# Mega_Stepper_Shield_Integrated.net
KiCad netlist of a schematic drawn in EAGLE
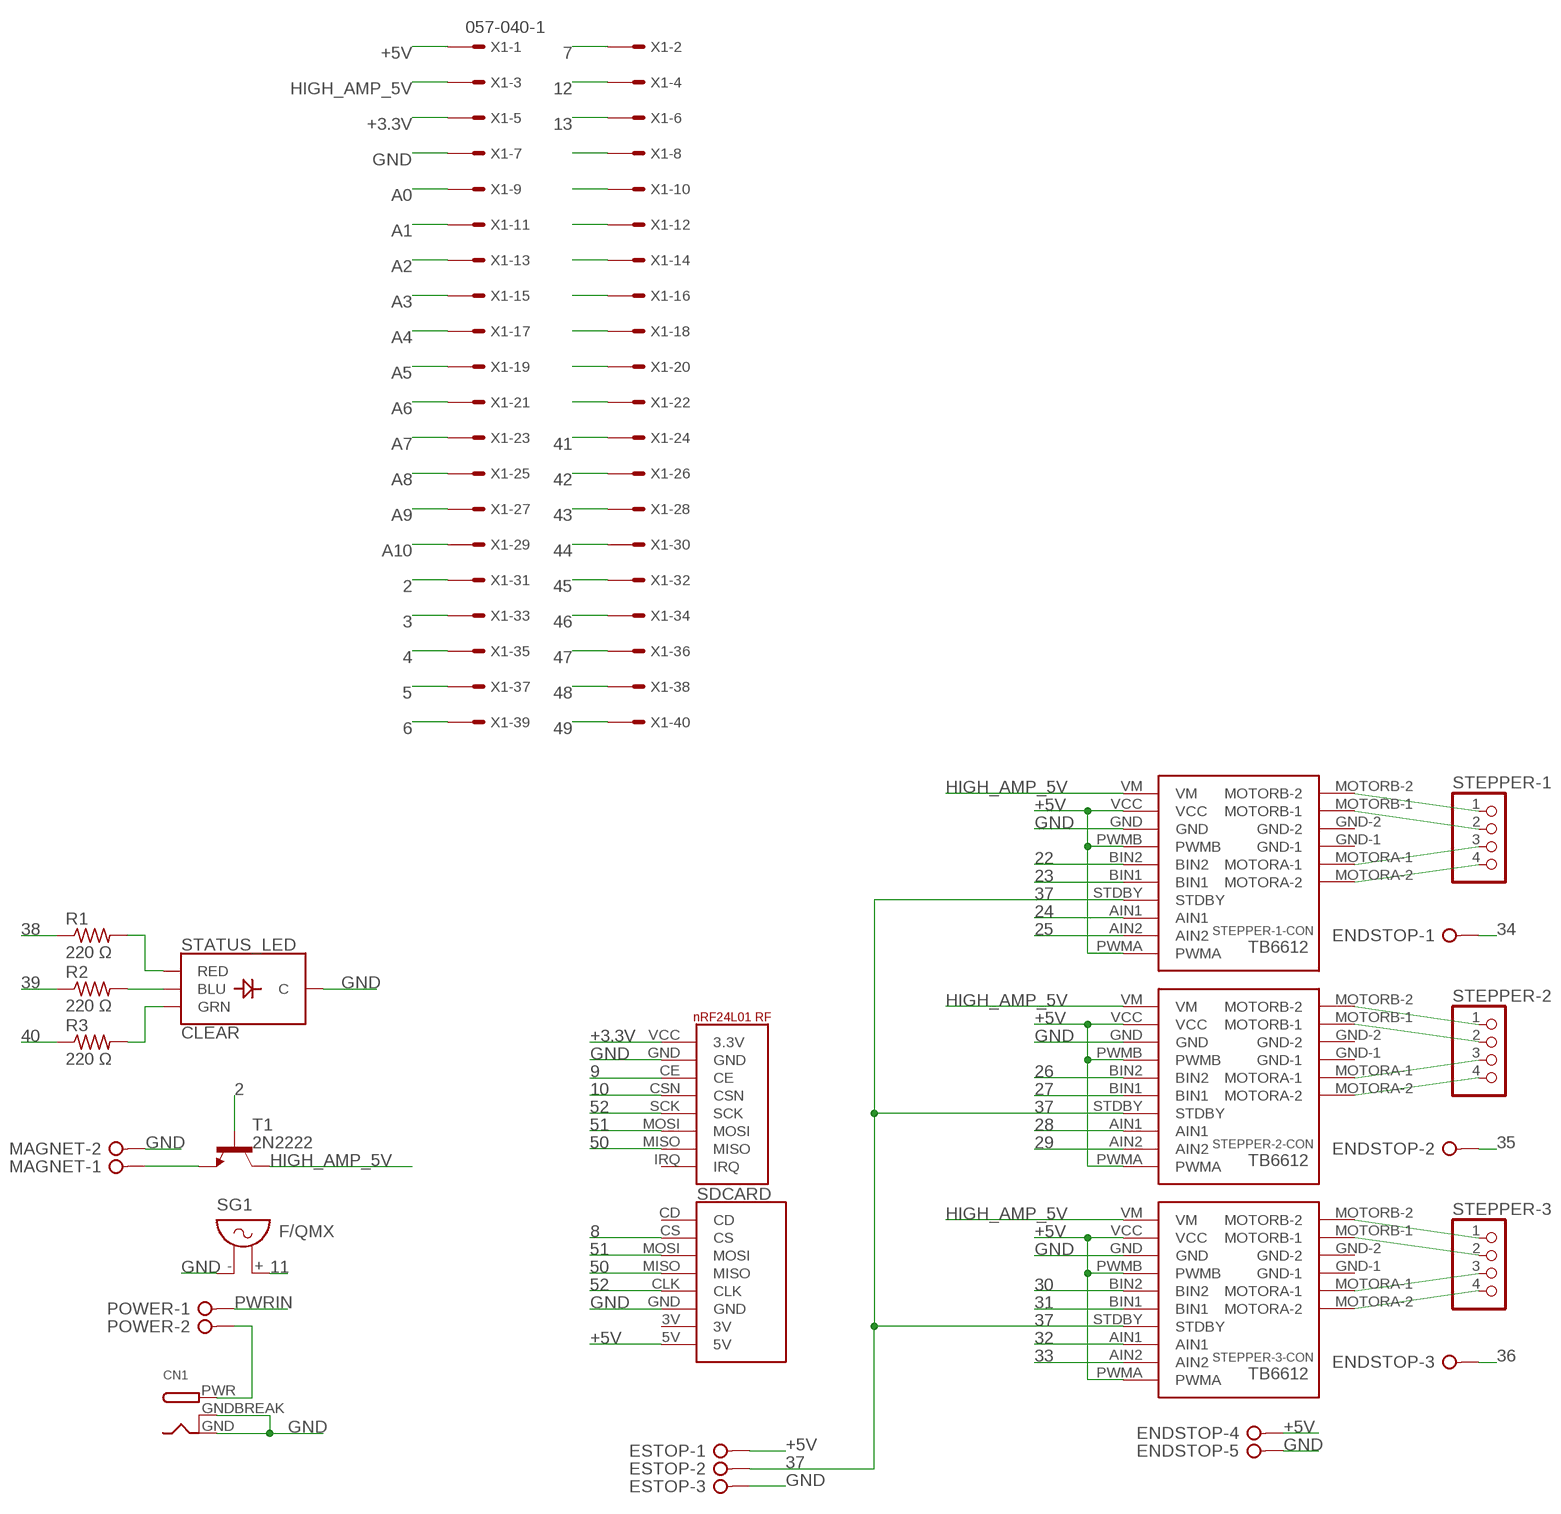
[diagram p0: schematic, sheet 1]
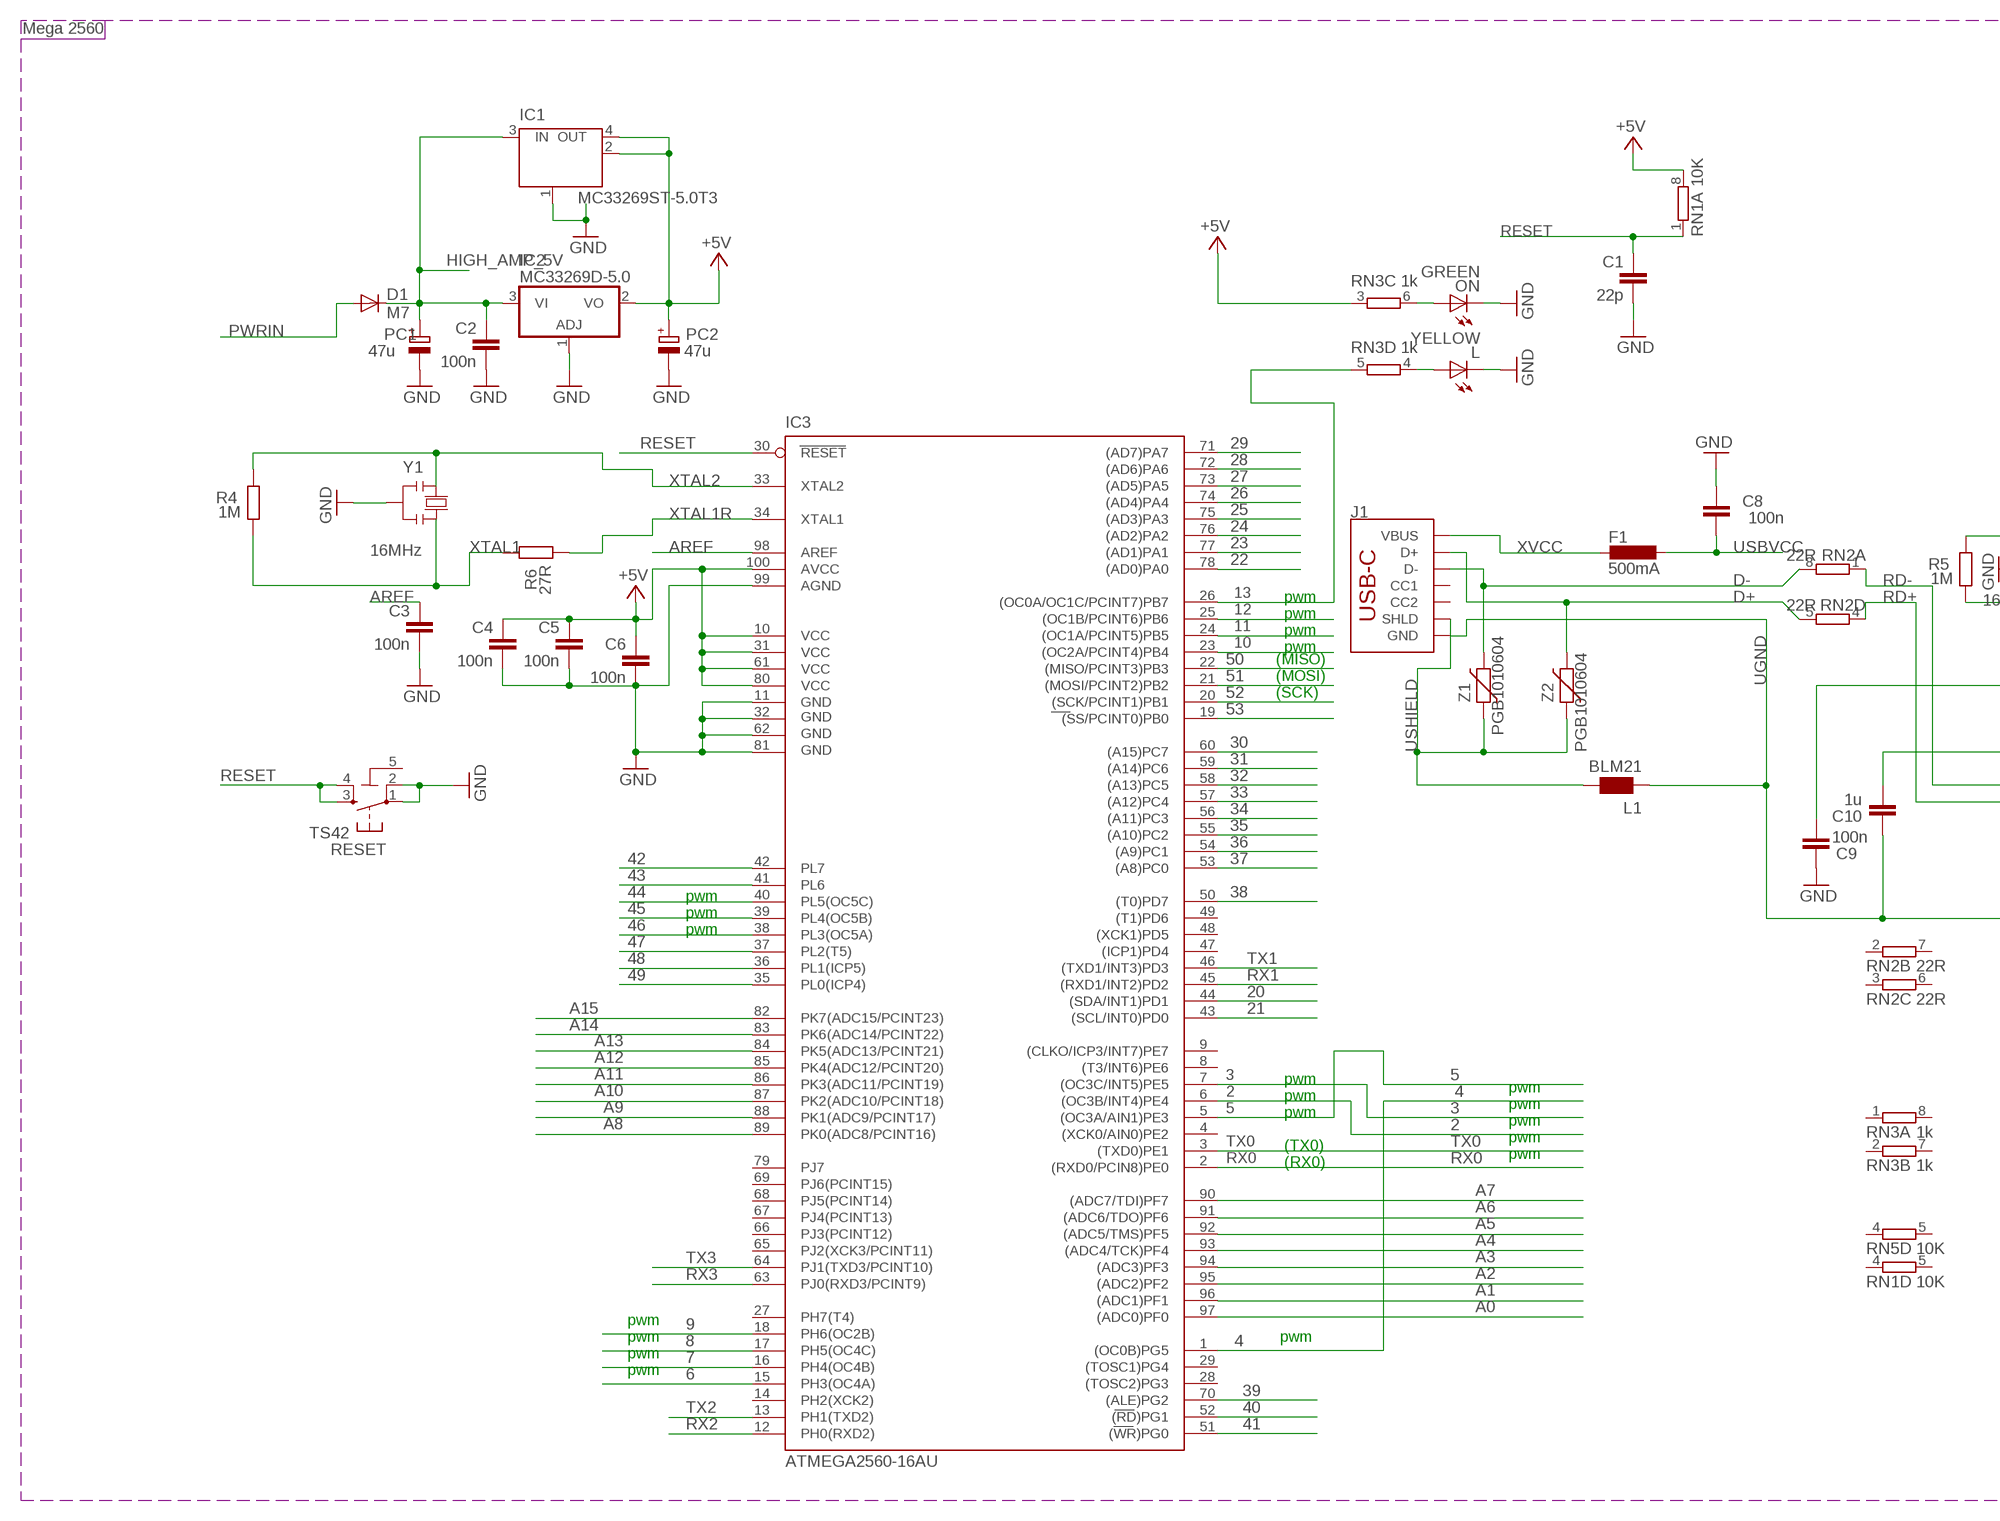
[diagram p1: schematic, sheet 2, part 1 of 2]
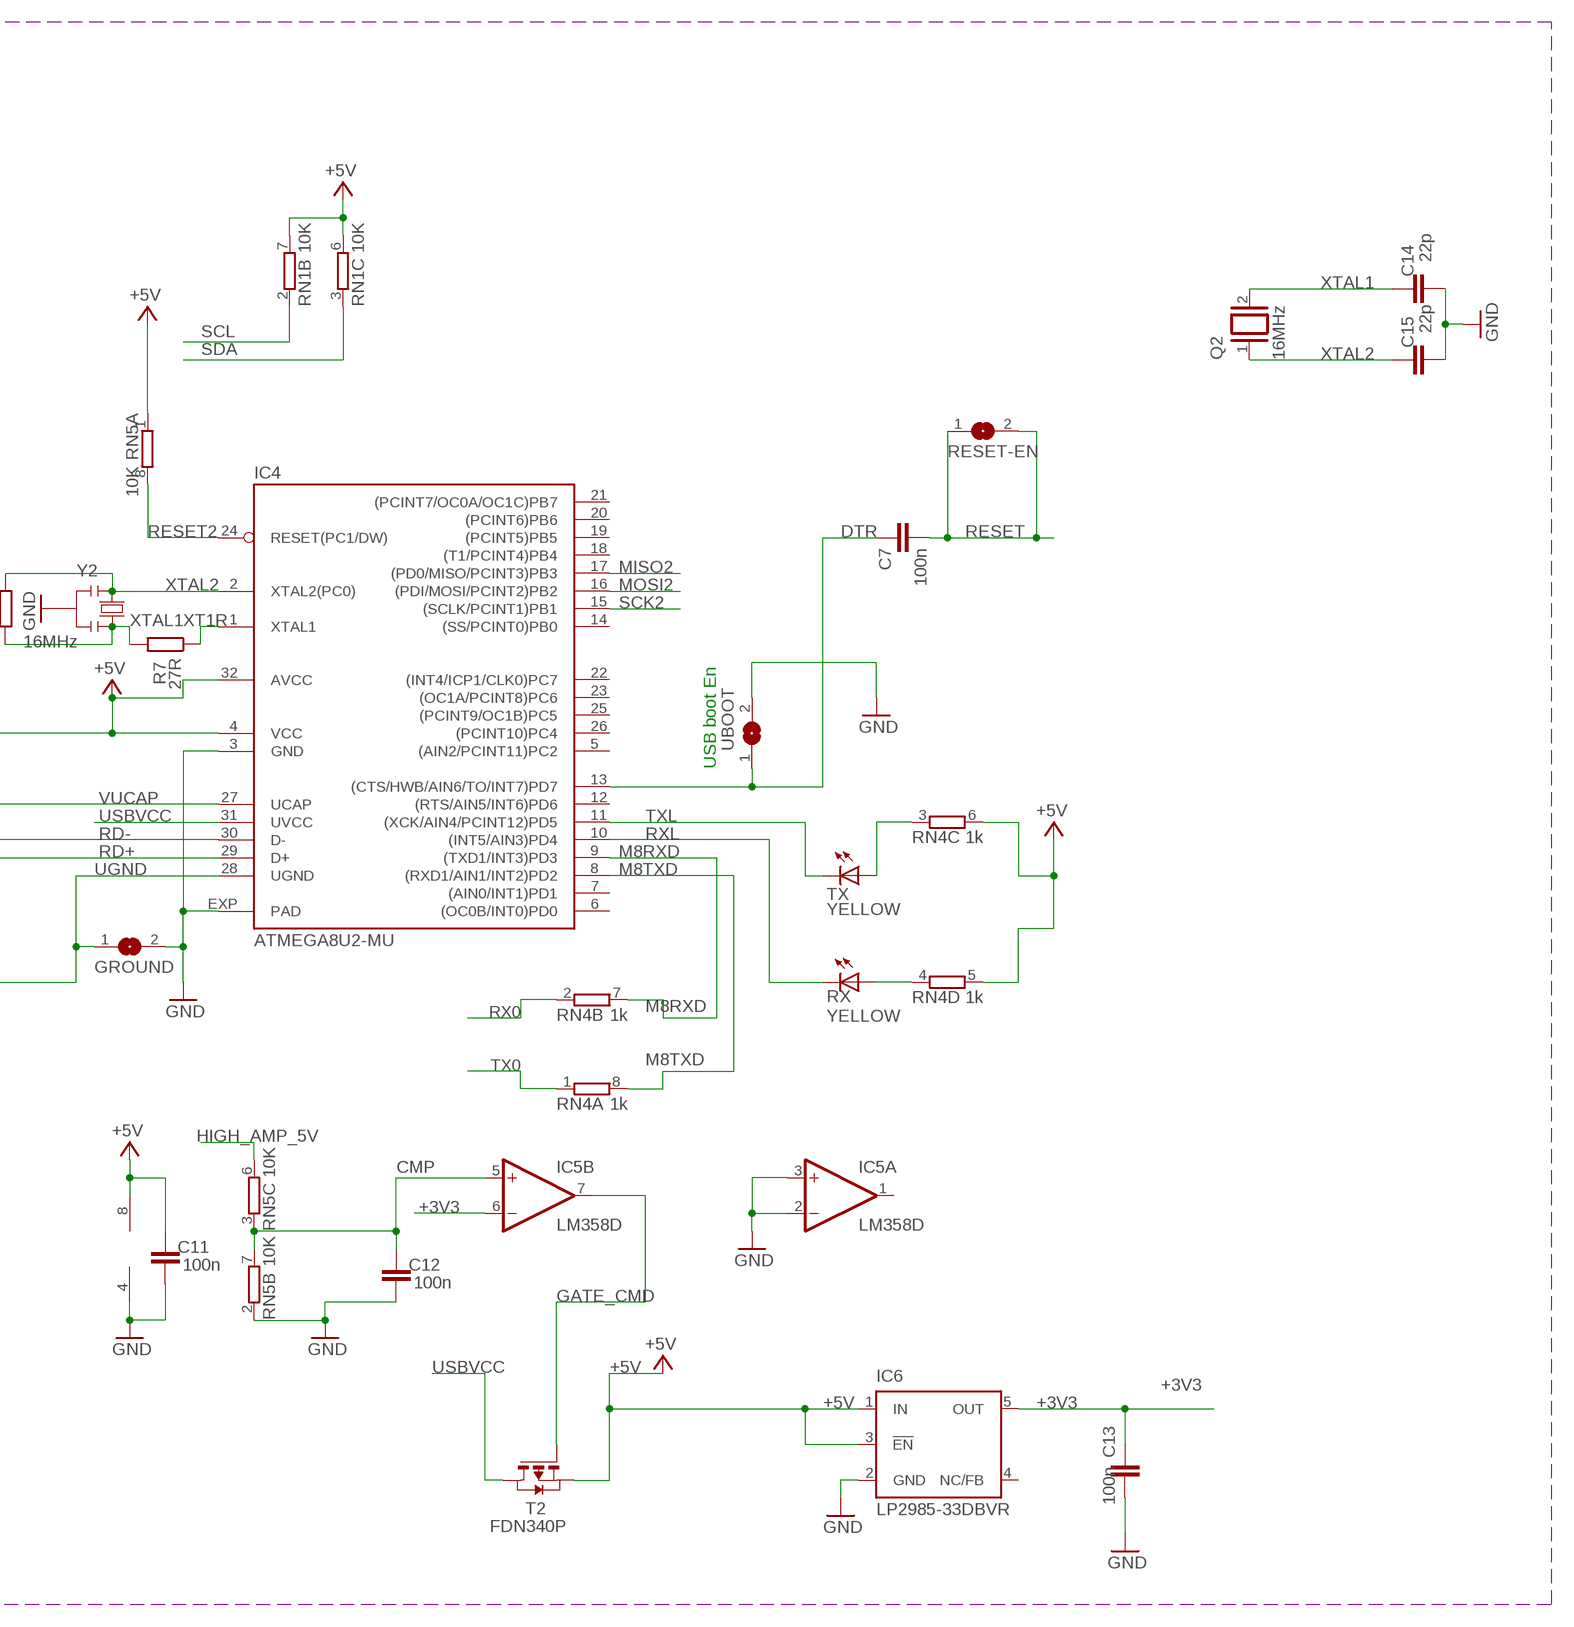
[diagram p2: schematic, sheet 2, part 2 of 2]

(export (version "E")
  (design (tool "Eeschema 10.0.6"))
  (components
    (comp (ref "CN1")
      (value "DCBARRELPTH")
      (footprint "eagle-import:DCJACK_2MM_PTH")
      (libsource (lib "eagle-import") (part "DCBARRELPTH"))
    )
    (comp (ref "ENDSTOP")
      (value "W237-05P")
      (footprint "eagle-import:W237-5P")
      (libsource (lib "eagle-import") (part "W237-05P"))
    )
    (comp (ref "ESTOP")
      (value "W237-3E")
      (footprint "eagle-import:W237-3E")
      (libsource (lib "eagle-import") (part "W237-3E"))
    )
    (comp (ref "MAGNET")
      (value "W237-02P")
      (footprint "eagle-import:W237-132")
      (libsource (lib "eagle-import") (part "W237-02P"))
    )
    (comp (ref "POWER")
      (value "W237-02P")
      (footprint "eagle-import:W237-132")
      (libsource (lib "eagle-import") (part "W237-02P"))
    )
    (comp (ref "R1")
      (value "220 Ω")
      (footprint "eagle-import:0204_7")
      (libsource (lib "eagle-import") (part "R-US_0204/7"))
    )
    (comp (ref "R2")
      (value "220 Ω")
      (footprint "eagle-import:0204_7")
      (libsource (lib "eagle-import") (part "R-US_0204/7"))
    )
    (comp (ref "R3")
      (value "220 Ω")
      (footprint "eagle-import:0204_7")
      (libsource (lib "eagle-import") (part "R-US_0204/7"))
    )
    (comp (ref "SDCARD")
      (value "MICRO_SD_BREAKOUT")
      (footprint "eagle-import:MICROSDCARDBREAKOUT")
      (libsource (lib "eagle-import") (part "MICRO_SD_BREAKOUT"))
    )
    (comp (ref "SG1")
      (value "F/QMX")
      (footprint "eagle-import:F_QMX")
      (libsource (lib "eagle-import") (part "F/QMX"))
    )
    (comp (ref "STATUS_LED")
      (value "CLEAR")
      (footprint "eagle-import:LED-RGB-THRU")
      (libsource (lib "eagle-import") (part "LED-RGB-CCCLEAR"))
    )
    (comp (ref "STEPPER-1")
      (value "PINHD-1X4")
      (footprint "eagle-import:1X04")
      (libsource (lib "eagle-import") (part "PINHD-1X4"))
    )
    (comp (ref "STEPPER-1-CON")
      (value "TB6612-BREAKOUT-MOTOR-CONTROLLER")
      (footprint "eagle-import:TB6612-HEADERS")
      (libsource (lib "eagle-import") (part "TB6612-BREAKOUT-MOTOR-CONTROLLER"))
    )
    (comp (ref "STEPPER-2")
      (value "PINHD-1X4")
      (footprint "eagle-import:1X04")
      (libsource (lib "eagle-import") (part "PINHD-1X4"))
    )
    (comp (ref "STEPPER-2-CON")
      (value "TB6612-BREAKOUT-MOTOR-CONTROLLER")
      (footprint "eagle-import:TB6612-HEADERS")
      (libsource (lib "eagle-import") (part "TB6612-BREAKOUT-MOTOR-CONTROLLER"))
    )
    (comp (ref "STEPPER-3")
      (value "PINHD-1X4")
      (footprint "eagle-import:1X04")
      (libsource (lib "eagle-import") (part "PINHD-1X4"))
    )
    (comp (ref "STEPPER-3-CON")
      (value "TB6612-BREAKOUT-MOTOR-CONTROLLER")
      (footprint "eagle-import:TB6612-HEADERS")
      (libsource (lib "eagle-import") (part "TB6612-BREAKOUT-MOTOR-CONTROLLER"))
    )
    (comp (ref "T1")
      (value "2N2222")
      (footprint "eagle-import:TO92-EBC-OVAL")
      (libsource (lib "eagle-import") (part "2N2222"))
    )
    (comp (ref "U$1")
      (value "NRF24L01_RF_MODULE")
      (footprint "eagle-import:NRF24L01RF")
      (libsource (lib "eagle-import") (part "NRF24L01_RF_MODULE"))
    )
    (comp (ref "X1")
      (value "057-040-1")
      (footprint "eagle-import:057-040-1")
      (libsource (lib "eagle-import") (part "057-040-1"))
    )
    (comp (ref "C1")
      (value "22p")
      (footprint "eagle-import:C0603-ROUND")
      (libsource (lib "eagle-import") (part "C-EU0603-RND"))
    )
    (comp (ref "C2")
      (value "100n")
      (footprint "eagle-import:C0603-ROUND")
      (libsource (lib "eagle-import") (part "C-EU0603-RND"))
    )
    (comp (ref "C3")
      (value "100n")
      (footprint "eagle-import:C0603-ROUND")
      (libsource (lib "eagle-import") (part "C-EU0603-RND"))
    )
    (comp (ref "C4")
      (value "100n")
      (footprint "eagle-import:C0603-ROUND")
      (libsource (lib "eagle-import") (part "C-EU0603-RND"))
    )
    (comp (ref "C5")
      (value "100n")
      (footprint "eagle-import:C0603-ROUND")
      (libsource (lib "eagle-import") (part "C-EU0603-RND"))
    )
    (comp (ref "C6")
      (value "100n")
      (footprint "eagle-import:C0603-ROUND")
      (libsource (lib "eagle-import") (part "C-EU0603-RND"))
    )
    (comp (ref "C7")
      (value "100n")
      (footprint "eagle-import:C0603-ROUND")
      (libsource (lib "eagle-import") (part "C-EU0603-RND"))
    )
    (comp (ref "C8")
      (value "100n")
      (footprint "eagle-import:C0603")
      (libsource (lib "eagle-import") (part "rcl_C-EUC0603"))
    )
    (comp (ref "C9")
      (value "100n")
      (footprint "eagle-import:C0603-ROUND")
      (libsource (lib "eagle-import") (part "C-EU0603-RND"))
    )
    (comp (ref "C10")
      (value "1u")
      (footprint "eagle-import:C0603-ROUND")
      (libsource (lib "eagle-import") (part "C-EU0603-RND"))
    )
    (comp (ref "C11")
      (value "100n")
      (footprint "eagle-import:C0603")
      (libsource (lib "eagle-import") (part "rcl_C-EUC0603"))
    )
    (comp (ref "C12")
      (value "100n")
      (footprint "eagle-import:C0603-ROUND")
      (libsource (lib "eagle-import") (part "C-EU0603-RND"))
    )
    (comp (ref "C13")
      (value "100n")
      (footprint "eagle-import:C0603-ROUND")
      (libsource (lib "eagle-import") (part "C-EU0603-RND"))
    )
    (comp (ref "C14")
      (value "22p")
      (footprint "eagle-import:C0603-ROUND")
      (libsource (lib "eagle-import") (part "C-EU0603-RND"))
    )
    (comp (ref "C15")
      (value "22p")
      (footprint "eagle-import:C0603-ROUND")
      (libsource (lib "eagle-import") (part "C-EU0603-RND"))
    )
    (comp (ref "D1")
      (value "M7")
      (footprint "eagle-import:SMB")
      (libsource (lib "eagle-import") (part "DIODE-SMB"))
    )
    (comp (ref "F1")
      (value "500mA")
      (footprint "eagle-import:L1812")
      (libsource (lib "eagle-import") (part "L-EUL1812"))
    )
    (comp (ref "GROUND")
      (value "SJ")
      (footprint "eagle-import:SJ")
      (libsource (lib "eagle-import") (part "SJ"))
    )
    (comp (ref "IC1")
      (value "MC33269ST-5.0T3")
      (footprint "eagle-import:SOT223")
      (libsource (lib "eagle-import") (part "MC33269ST-3.3T3"))
    )
    (comp (ref "IC2")
      (value "MC33269D-5.0")
      (footprint "eagle-import:DPACK")
      (libsource (lib "eagle-import") (part "MC33269?D-5.0"))
    )
    (comp (ref "IC3")
      (value "ATMEGA2560-16AU")
      (footprint "eagle-import:TQFP100")
      (libsource (lib "eagle-import") (part "ATMEGAAU1280-16"))
    )
    (comp (ref "IC4")
      (value "ATMEGA8U2-MU")
      (footprint "eagle-import:QFN32")
      (libsource (lib "eagle-import") (part "ATMEGA8U2-MU"))
    )
    (comp (ref "IC5")
      (value "LM358D")
      (footprint "eagle-import:SO08")
      (libsource (lib "eagle-import") (part "LM358D"))
    )
    (comp (ref "IC6")
      (value "LP2985-33DBVR")
      (footprint "eagle-import:SOT23-DBV")
      (libsource (lib "eagle-import") (part "TPS77033"))
    )
    (comp (ref "J1")
      (value "USB_C_2-LAYER_PADS")
      (footprint "eagle-import:USB-C-16P-2LAYER-PADS")
      (libsource (lib "eagle-import") (part "USB_C_2-LAYER_PADS"))
    )
    (comp (ref "L")
      (value "YELLOW")
      (footprint "eagle-import:CHIP-LED0805")
      (libsource (lib "eagle-import") (part "LEDCHIP-LED0805"))
    )
    (comp (ref "L1")
      (value "BLM21")
      (footprint "eagle-import:0805")
      (libsource (lib "eagle-import") (part "WE-CBF_0805"))
    )
    (comp (ref "ON")
      (value "GREEN")
      (footprint "eagle-import:CHIP-LED0805")
      (libsource (lib "eagle-import") (part "LEDCHIP-LED0805"))
    )
    (comp (ref "PC1")
      (value "47u")
      (footprint "eagle-import:PANASONIC_D")
      (libsource (lib "eagle-import") (part "CPOL-EUD"))
    )
    (comp (ref "PC2")
      (value "47u")
      (footprint "eagle-import:PANASONIC_D")
      (libsource (lib "eagle-import") (part "CPOL-EUD"))
    )
    (comp (ref "Q2")
      (value "16MHz")
      (footprint "eagle-import:QS")
      (libsource (lib "eagle-import") (part "XTAL/S"))
    )
    (comp (ref "R4")
      (value "1M")
      (footprint "eagle-import:R0603-ROUND")
      (libsource (lib "eagle-import") (part "R-EU_R0603"))
    )
    (comp (ref "R5")
      (value "1M")
      (footprint "eagle-import:R0603-ROUND")
      (libsource (lib "eagle-import") (part "R-EU_R0603"))
    )
    (comp (ref "R6")
      (value "27R")
      (footprint "eagle-import:R0603-ROUND")
      (libsource (lib "eagle-import") (part "R-EU_R0603"))
    )
    (comp (ref "R7")
      (value "27R")
      (footprint "eagle-import:R0603-ROUND")
      (libsource (lib "eagle-import") (part "R-EU_R0603"))
    )
    (comp (ref "RESET")
      (value "TS42")
      (footprint "eagle-import:TS42")
      (libsource (lib "eagle-import") (part "TS42"))
    )
    (comp (ref "RESET-EN")
      (value "SJ")
      (footprint "eagle-import:SJ")
      (libsource (lib "eagle-import") (part "SJ"))
    )
    (comp (ref "RN1")
      (value "10K")
      (footprint "eagle-import:CAT16")
      (libsource (lib "eagle-import") (part "4R-NCAT16"))
    )
    (comp (ref "RN2")
      (value "22R")
      (footprint "eagle-import:CAY16")
      (libsource (lib "eagle-import") (part "4R-NCAY16"))
    )
    (comp (ref "RN3")
      (value "1k")
      (footprint "eagle-import:CAY16")
      (libsource (lib "eagle-import") (part "4R-NCAY16"))
    )
    (comp (ref "RN4")
      (value "1k")
      (footprint "eagle-import:CAY16")
      (libsource (lib "eagle-import") (part "4R-NCAY16"))
    )
    (comp (ref "RN5")
      (value "10K")
      (footprint "eagle-import:CAT16")
      (libsource (lib "eagle-import") (part "4R-NCAT16"))
    )
    (comp (ref "RX")
      (value "YELLOW")
      (footprint "eagle-import:CHIP-LED0805")
      (libsource (lib "eagle-import") (part "LEDCHIP-LED0805"))
    )
    (comp (ref "T2")
      (value "FDN340P")
      (footprint "eagle-import:SOT-23")
      (libsource (lib "eagle-import") (part "PMOSSOT23"))
    )
    (comp (ref "TX")
      (value "YELLOW")
      (footprint "eagle-import:CHIP-LED0805")
      (libsource (lib "eagle-import") (part "LEDCHIP-LED0805"))
    )
    (comp (ref "UBOOT")
      (value "SJ")
      (footprint "eagle-import:SJ")
      (libsource (lib "eagle-import") (part "SJ"))
    )
    (comp (ref "Y1")
      (value "16MHz")
      (footprint "eagle-import:RESONATOR")
      (libsource (lib "eagle-import") (part "RESONATORMU"))
    )
    (comp (ref "Y2")
      (value "16MHz")
      (footprint "eagle-import:RESONATOR")
      (libsource (lib "eagle-import") (part "RESONATORMU"))
    )
    (comp (ref "Z1")
      (value "PGB1010604")
      (footprint "eagle-import:CT_CN0603")
      (libsource (lib "eagle-import") (part "VARISTORCN0603"))
    )
    (comp (ref "Z2")
      (value "PGB1010604")
      (footprint "eagle-import:CT_CN0603")
      (libsource (lib "eagle-import") (part "VARISTORCN0603"))
    )
  )
  (nets
    (net (code "1") (name "+3.3V") (class "Default")
      (node (ref "U$1") (pin "VCC") (pinfunction "3.3V_VCC") (pintype "bidirectional"))
      (node (ref "X1") (pin "5") (pinfunction "S_5") (pintype "passive"))
    )
    (net (code "2") (name "+3V3") (class "Default")
      (node (ref "C13") (pin "2") (pinfunction "2_2") (pintype "passive"))
      (node (ref "IC5") (pin "6") (pinfunction "-IN_6") (pintype "input"))
      (node (ref "IC6") (pin "5") (pinfunction "OUT_5") (pintype "passive"))
    )
    (net (code "3") (name "+5V") (class "Default")
      (node (ref "C11") (pin "2") (pinfunction "2_2") (pintype "passive"))
      (node (ref "C4") (pin "1") (pinfunction "1_1") (pintype "passive"))
      (node (ref "C5") (pin "1") (pinfunction "1_1") (pintype "passive"))
      (node (ref "C6") (pin "1") (pinfunction "1_1") (pintype "passive"))
      (node (ref "C9") (pin "1") (pinfunction "1_1") (pintype "passive"))
      (node (ref "ENDSTOP") (pin "4") (pinfunction "KL_4") (pintype "passive"))
      (node (ref "ESTOP") (pin "1") (pinfunction "KL_1") (pintype "passive"))
      (node (ref "IC1") (pin "2") (pinfunction "OUT_2") (pintype "passive"))
      (node (ref "IC1") (pin "4") (pinfunction "OUT_4") (pintype "passive"))
      (node (ref "IC2") (pin "2") (pinfunction "VO_2") (pintype "passive"))
      (node (ref "IC3") (pin "10") (pinfunction "VCC_10") (pintype "power_in"))
      (node (ref "IC3") (pin "100") (pinfunction "AVCC_100") (pintype "power_in"))
      (node (ref "IC3") (pin "31") (pinfunction "VCC1_31") (pintype "power_in"))
      (node (ref "IC3") (pin "61") (pinfunction "VCC2_61") (pintype "power_in"))
      (node (ref "IC3") (pin "80") (pinfunction "VCC3_80") (pintype "power_in"))
      (node (ref "IC4") (pin "32") (pinfunction "AVCC_32") (pintype "power_in"))
      (node (ref "IC4") (pin "4") (pinfunction "VCC_4") (pintype "power_in"))
      (node (ref "IC5") (pin "8") (pinfunction "V+_8") (pintype "power_in"))
      (node (ref "IC6") (pin "1") (pinfunction "IN_1") (pintype "input"))
      (node (ref "IC6") (pin "3") (pinfunction "~{EN}_3") (pintype "input"))
      (node (ref "PC2") (pin "+") (pinfunction "+_+") (pintype "passive"))
      (node (ref "RN1") (pin "6") (pinfunction "2_6") (pintype "passive"))
      (node (ref "RN1") (pin "7") (pinfunction "2_7") (pintype "passive"))
      (node (ref "RN1") (pin "8") (pinfunction "2_8") (pintype "passive"))
      (node (ref "RN3") (pin "3") (pinfunction "1_3") (pintype "passive"))
      (node (ref "RN4") (pin "5") (pinfunction "2_5") (pintype "passive"))
      (node (ref "RN4") (pin "6") (pinfunction "2_6") (pintype "passive"))
      (node (ref "RN5") (pin "1") (pinfunction "1_1") (pintype "passive"))
      (node (ref "SDCARD") (pin "5V") (pinfunction "5V_5V") (pintype "bidirectional"))
      (node (ref "STEPPER-1-CON") (pin "PWMA") (pinfunction "PWMA_PWMA") (pintype "bidirectional"))
      (node (ref "STEPPER-1-CON") (pin "PWMB") (pinfunction "PWMB_PWMB") (pintype "bidirectional"))
      (node (ref "STEPPER-1-CON") (pin "VCC") (pinfunction "VCC_VCC") (pintype "bidirectional"))
      (node (ref "STEPPER-2-CON") (pin "PWMA") (pinfunction "PWMA_PWMA") (pintype "bidirectional"))
      (node (ref "STEPPER-2-CON") (pin "PWMB") (pinfunction "PWMB_PWMB") (pintype "bidirectional"))
      (node (ref "STEPPER-2-CON") (pin "VCC") (pinfunction "VCC_VCC") (pintype "bidirectional"))
      (node (ref "STEPPER-3-CON") (pin "PWMA") (pinfunction "PWMA_PWMA") (pintype "bidirectional"))
      (node (ref "STEPPER-3-CON") (pin "PWMB") (pinfunction "PWMB_PWMB") (pintype "bidirectional"))
      (node (ref "STEPPER-3-CON") (pin "VCC") (pinfunction "VCC_VCC") (pintype "bidirectional"))
      (node (ref "T2") (pin "2") (pinfunction "S_2") (pintype "passive"))
      (node (ref "X1") (pin "1") (pinfunction "S_1") (pintype "passive"))
    )
    (net (code "4") (name "2") (class "Default")
      (node (ref "IC3") (pin "6") (pinfunction "(OC3B/INT4)PE4_6") (pintype "bidirectional"))
      (node (ref "T1") (pin "B") (pinfunction "B_B") (pintype "passive"))
      (node (ref "X1") (pin "31") (pinfunction "S_31") (pintype "passive"))
    )
    (net (code "5") (name "3") (class "Default")
      (node (ref "IC3") (pin "7") (pinfunction "(OC3C/INT5)PE5_7") (pintype "bidirectional"))
      (node (ref "X1") (pin "33") (pinfunction "S_33") (pintype "passive"))
    )
    (net (code "6") (name "4") (class "Default")
      (node (ref "IC3") (pin "1") (pinfunction "(OC0B)PG5_1") (pintype "bidirectional"))
      (node (ref "X1") (pin "35") (pinfunction "S_35") (pintype "passive"))
    )
    (net (code "7") (name "5") (class "Default")
      (node (ref "IC3") (pin "5") (pinfunction "(OC3A/AIN1)PE3_5") (pintype "bidirectional"))
      (node (ref "X1") (pin "37") (pinfunction "S_37") (pintype "passive"))
    )
    (net (code "8") (name "5-GND") (class "Default")
      (node (ref "RESET") (pin "5") (pinfunction "5-GND_5") (pintype "power_in"))
    )
    (net (code "9") (name "6") (class "Default")
      (node (ref "IC3") (pin "15") (pinfunction "PH3(OC4A)_15") (pintype "bidirectional"))
      (node (ref "X1") (pin "39") (pinfunction "S_39") (pintype "passive"))
    )
    (net (code "10") (name "7") (class "Default")
      (node (ref "IC3") (pin "16") (pinfunction "PH4(OC4B)_16") (pintype "bidirectional"))
      (node (ref "X1") (pin "2") (pinfunction "S_2") (pintype "passive"))
    )
    (net (code "11") (name "8") (class "Default")
      (node (ref "IC3") (pin "17") (pinfunction "PH5(OC4C)_17") (pintype "bidirectional"))
      (node (ref "SDCARD") (pin "CS") (pinfunction "CS_CS") (pintype "bidirectional"))
    )
    (net (code "12") (name "9") (class "Default")
      (node (ref "IC3") (pin "18") (pinfunction "PH6(OC2B)_18") (pintype "bidirectional"))
      (node (ref "U$1") (pin "CE") (pinfunction "CE_CE") (pintype "bidirectional"))
    )
    (net (code "13") (name "10") (class "Default")
      (node (ref "IC3") (pin "23") (pinfunction "(OC2A/PCINT4)PB4_23") (pintype "bidirectional"))
      (node (ref "U$1") (pin "CSN") (pinfunction "CSN_CSN") (pintype "bidirectional"))
    )
    (net (code "14") (name "11") (class "Default")
      (node (ref "IC3") (pin "24") (pinfunction "(OC1A/PCINT5)PB5_24") (pintype "bidirectional"))
      (node (ref "SG1") (pin "+") (pinfunction "2_+") (pintype "passive"))
    )
    (net (code "15") (name "12") (class "Default")
      (node (ref "IC3") (pin "25") (pinfunction "(OC1B/PCINT6)PB6_25") (pintype "bidirectional"))
      (node (ref "X1") (pin "4") (pinfunction "S_4") (pintype "passive"))
    )
    (net (code "16") (name "13") (class "Default")
      (node (ref "IC3") (pin "26") (pinfunction "(OC0A/OC1C/PCINT7)PB7_26") (pintype "bidirectional"))
      (node (ref "RN3") (pin "5") (pinfunction "2_5") (pintype "passive"))
      (node (ref "X1") (pin "6") (pinfunction "S_6") (pintype "passive"))
    )
    (net (code "17") (name "20") (class "Default")
      (node (ref "IC3") (pin "44") (pinfunction "(SDA/INT1)PD1_44") (pintype "bidirectional"))
    )
    (net (code "18") (name "21") (class "Default")
      (node (ref "IC3") (pin "43") (pinfunction "(SCL/INT0)PD0_43") (pintype "bidirectional"))
    )
    (net (code "19") (name "22") (class "Default")
      (node (ref "IC3") (pin "78") (pinfunction "(AD0)PA0_78") (pintype "bidirectional"))
      (node (ref "STEPPER-1-CON") (pin "BIN2") (pinfunction "BIN2_BIN2") (pintype "bidirectional"))
    )
    (net (code "20") (name "23") (class "Default")
      (node (ref "IC3") (pin "77") (pinfunction "(AD1)PA1_77") (pintype "bidirectional"))
      (node (ref "STEPPER-1-CON") (pin "BIN1") (pinfunction "BIN1_BIN1") (pintype "bidirectional"))
    )
    (net (code "21") (name "24") (class "Default")
      (node (ref "IC3") (pin "76") (pinfunction "(AD2)PA2_76") (pintype "bidirectional"))
      (node (ref "STEPPER-1-CON") (pin "AIN1") (pinfunction "AIN1_AIN1") (pintype "bidirectional"))
    )
    (net (code "22") (name "25") (class "Default")
      (node (ref "IC3") (pin "75") (pinfunction "(AD3)PA3_75") (pintype "bidirectional"))
      (node (ref "STEPPER-1-CON") (pin "AIN2") (pinfunction "AIN2_AIN2") (pintype "bidirectional"))
    )
    (net (code "23") (name "26") (class "Default")
      (node (ref "IC3") (pin "74") (pinfunction "(AD4)PA4_74") (pintype "bidirectional"))
      (node (ref "STEPPER-2-CON") (pin "BIN2") (pinfunction "BIN2_BIN2") (pintype "bidirectional"))
    )
    (net (code "24") (name "27") (class "Default")
      (node (ref "IC3") (pin "73") (pinfunction "(AD5)PA5_73") (pintype "bidirectional"))
      (node (ref "STEPPER-2-CON") (pin "BIN1") (pinfunction "BIN1_BIN1") (pintype "bidirectional"))
    )
    (net (code "25") (name "28") (class "Default")
      (node (ref "IC3") (pin "72") (pinfunction "(AD6)PA6_72") (pintype "bidirectional"))
      (node (ref "STEPPER-2-CON") (pin "AIN1") (pinfunction "AIN1_AIN1") (pintype "bidirectional"))
    )
    (net (code "26") (name "29") (class "Default")
      (node (ref "IC3") (pin "71") (pinfunction "(AD7)PA7_71") (pintype "bidirectional"))
      (node (ref "STEPPER-2-CON") (pin "AIN2") (pinfunction "AIN2_AIN2") (pintype "bidirectional"))
    )
    (net (code "27") (name "30") (class "Default")
      (node (ref "IC3") (pin "60") (pinfunction "(A15)PC7_60") (pintype "bidirectional"))
      (node (ref "STEPPER-3-CON") (pin "BIN2") (pinfunction "BIN2_BIN2") (pintype "bidirectional"))
    )
    (net (code "28") (name "31") (class "Default")
      (node (ref "IC3") (pin "59") (pinfunction "(A14)PC6_59") (pintype "bidirectional"))
      (node (ref "STEPPER-3-CON") (pin "BIN1") (pinfunction "BIN1_BIN1") (pintype "bidirectional"))
    )
    (net (code "29") (name "32") (class "Default")
      (node (ref "IC3") (pin "58") (pinfunction "(A13)PC5_58") (pintype "bidirectional"))
      (node (ref "STEPPER-3-CON") (pin "AIN1") (pinfunction "AIN1_AIN1") (pintype "bidirectional"))
    )
    (net (code "30") (name "33") (class "Default")
      (node (ref "IC3") (pin "57") (pinfunction "(A12)PC4_57") (pintype "bidirectional"))
      (node (ref "STEPPER-3-CON") (pin "AIN2") (pinfunction "AIN2_AIN2") (pintype "bidirectional"))
    )
    (net (code "31") (name "34") (class "Default")
      (node (ref "ENDSTOP") (pin "1") (pinfunction "KL_1") (pintype "passive"))
      (node (ref "IC3") (pin "56") (pinfunction "(A11)PC3_56") (pintype "bidirectional"))
    )
    (net (code "32") (name "35") (class "Default")
      (node (ref "ENDSTOP") (pin "2") (pinfunction "KL_2") (pintype "passive"))
      (node (ref "IC3") (pin "55") (pinfunction "(A10)PC2_55") (pintype "bidirectional"))
    )
    (net (code "33") (name "36") (class "Default")
      (node (ref "ENDSTOP") (pin "3") (pinfunction "KL_3") (pintype "passive"))
      (node (ref "IC3") (pin "54") (pinfunction "(A9)PC1_54") (pintype "bidirectional"))
    )
    (net (code "34") (name "37") (class "Default")
      (node (ref "ESTOP") (pin "2") (pinfunction "KL_2") (pintype "passive"))
      (node (ref "IC3") (pin "53") (pinfunction "(A8)PC0_53") (pintype "bidirectional"))
      (node (ref "STEPPER-1-CON") (pin "STDBY") (pinfunction "STDBY_STDBY") (pintype "bidirectional"))
      (node (ref "STEPPER-2-CON") (pin "STDBY") (pinfunction "STDBY_STDBY") (pintype "bidirectional"))
      (node (ref "STEPPER-3-CON") (pin "STDBY") (pinfunction "STDBY_STDBY") (pintype "bidirectional"))
    )
    (net (code "35") (name "38") (class "Default")
      (node (ref "IC3") (pin "50") (pinfunction "(T0)PD7_50") (pintype "bidirectional"))
      (node (ref "R1") (pin "1") (pinfunction "1_1") (pintype "passive"))
    )
    (net (code "36") (name "39") (class "Default")
      (node (ref "IC3") (pin "70") (pinfunction "(ALE)PG2_70") (pintype "bidirectional"))
      (node (ref "R2") (pin "1") (pinfunction "1_1") (pintype "passive"))
    )
    (net (code "37") (name "40") (class "Default")
      (node (ref "IC3") (pin "52") (pinfunction "(RD)PG1_52") (pintype "bidirectional"))
      (node (ref "R3") (pin "1") (pinfunction "1_1") (pintype "passive"))
      (node (ref "X1") (pin "22") (pinfunction "S_22") (pintype "passive"))
    )
    (net (code "38") (name "41") (class "Default")
      (node (ref "IC3") (pin "51") (pinfunction "(WR)PG0_51") (pintype "bidirectional"))
      (node (ref "X1") (pin "24") (pinfunction "S_24") (pintype "passive"))
    )
    (net (code "39") (name "42") (class "Default")
      (node (ref "IC3") (pin "42") (pinfunction "PL7_42") (pintype "bidirectional"))
      (node (ref "X1") (pin "26") (pinfunction "S_26") (pintype "passive"))
    )
    (net (code "40") (name "43") (class "Default")
      (node (ref "IC3") (pin "41") (pinfunction "PL6_41") (pintype "bidirectional"))
      (node (ref "X1") (pin "28") (pinfunction "S_28") (pintype "passive"))
    )
    (net (code "41") (name "44") (class "Default")
      (node (ref "IC3") (pin "40") (pinfunction "PL5(OC5C)_40") (pintype "bidirectional"))
      (node (ref "X1") (pin "30") (pinfunction "S_30") (pintype "passive"))
    )
    (net (code "42") (name "45") (class "Default")
      (node (ref "IC3") (pin "39") (pinfunction "PL4(OC5B)_39") (pintype "bidirectional"))
      (node (ref "X1") (pin "32") (pinfunction "S_32") (pintype "passive"))
    )
    (net (code "43") (name "46") (class "Default")
      (node (ref "IC3") (pin "38") (pinfunction "PL3(OC5A)_38") (pintype "bidirectional"))
      (node (ref "X1") (pin "34") (pinfunction "S_34") (pintype "passive"))
    )
    (net (code "44") (name "47") (class "Default")
      (node (ref "IC3") (pin "37") (pinfunction "PL2(T5)_37") (pintype "bidirectional"))
      (node (ref "X1") (pin "36") (pinfunction "S_36") (pintype "passive"))
    )
    (net (code "45") (name "48") (class "Default")
      (node (ref "IC3") (pin "36") (pinfunction "PL1(ICP5)_36") (pintype "bidirectional"))
      (node (ref "X1") (pin "38") (pinfunction "S_38") (pintype "passive"))
    )
    (net (code "46") (name "49") (class "Default")
      (node (ref "IC3") (pin "35") (pinfunction "PL0(ICP4)_35") (pintype "bidirectional"))
      (node (ref "X1") (pin "40") (pinfunction "S_40") (pintype "passive"))
    )
    (net (code "47") (name "50") (class "Default")
      (node (ref "IC3") (pin "22") (pinfunction "(MISO/PCINT3)PB3_22") (pintype "bidirectional"))
      (node (ref "SDCARD") (pin "MISO") (pinfunction "MISO_MISO") (pintype "bidirectional"))
      (node (ref "U$1") (pin "MISO") (pinfunction "MISO_MISO") (pintype "bidirectional"))
    )
    (net (code "48") (name "51") (class "Default")
      (node (ref "IC3") (pin "21") (pinfunction "(MOSI/PCINT2)PB2_21") (pintype "bidirectional"))
      (node (ref "SDCARD") (pin "MOSI") (pinfunction "MOSI_MOSI") (pintype "bidirectional"))
      (node (ref "U$1") (pin "MOSI") (pinfunction "MOSI_MOSI") (pintype "bidirectional"))
    )
    (net (code "49") (name "52") (class "Default")
      (node (ref "IC3") (pin "20") (pinfunction "(SCK/PCINT1)PB1_20") (pintype "bidirectional"))
      (node (ref "SDCARD") (pin "CLK") (pinfunction "CLK_CLK") (pintype "bidirectional"))
      (node (ref "U$1") (pin "SCK") (pinfunction "SCK_SCK") (pintype "bidirectional"))
    )
    (net (code "50") (name "53") (class "Default")
      (node (ref "IC3") (pin "19") (pinfunction "(SS/PCINT0)PB0_19") (pintype "bidirectional"))
    )
    (net (code "51") (name "A0") (class "Default")
      (node (ref "IC3") (pin "97") (pinfunction "(ADC0)PF0_97") (pintype "bidirectional"))
      (node (ref "X1") (pin "9") (pinfunction "S_9") (pintype "passive"))
    )
    (net (code "52") (name "A1") (class "Default")
      (node (ref "IC3") (pin "96") (pinfunction "(ADC1)PF1_96") (pintype "bidirectional"))
      (node (ref "X1") (pin "11") (pinfunction "S_11") (pintype "passive"))
    )
    (net (code "53") (name "A2") (class "Default")
      (node (ref "IC3") (pin "95") (pinfunction "(ADC2)PF2_95") (pintype "bidirectional"))
      (node (ref "X1") (pin "13") (pinfunction "S_13") (pintype "passive"))
    )
    (net (code "54") (name "A3") (class "Default")
      (node (ref "IC3") (pin "94") (pinfunction "(ADC3)PF3_94") (pintype "bidirectional"))
      (node (ref "X1") (pin "15") (pinfunction "S_15") (pintype "passive"))
    )
    (net (code "55") (name "A4") (class "Default")
      (node (ref "IC3") (pin "93") (pinfunction "(ADC4/TCK)PF4_93") (pintype "bidirectional"))
      (node (ref "X1") (pin "17") (pinfunction "S_17") (pintype "passive"))
    )
    (net (code "56") (name "A5") (class "Default")
      (node (ref "IC3") (pin "92") (pinfunction "(ADC5/TMS)PF5_92") (pintype "bidirectional"))
      (node (ref "X1") (pin "19") (pinfunction "S_19") (pintype "passive"))
    )
    (net (code "57") (name "A6") (class "Default")
      (node (ref "IC3") (pin "91") (pinfunction "(ADC6/TDO)PF6_91") (pintype "bidirectional"))
      (node (ref "X1") (pin "21") (pinfunction "S_21") (pintype "passive"))
    )
    (net (code "58") (name "A7") (class "Default")
      (node (ref "IC3") (pin "90") (pinfunction "(ADC7/TDI)PF7_90") (pintype "bidirectional"))
      (node (ref "X1") (pin "23") (pinfunction "S_23") (pintype "passive"))
    )
    (net (code "59") (name "A8") (class "Default")
      (node (ref "IC3") (pin "89") (pinfunction "PK0(ADC8/PCINT16)_89") (pintype "bidirectional"))
      (node (ref "X1") (pin "25") (pinfunction "S_25") (pintype "passive"))
    )
    (net (code "60") (name "A9") (class "Default")
      (node (ref "IC3") (pin "88") (pinfunction "PK1(ADC9/PCINT17)_88") (pintype "bidirectional"))
      (node (ref "X1") (pin "27") (pinfunction "S_27") (pintype "passive"))
    )
    (net (code "61") (name "A10") (class "Default")
      (node (ref "IC3") (pin "87") (pinfunction "PK2(ADC10/PCINT18)_87") (pintype "bidirectional"))
      (node (ref "X1") (pin "29") (pinfunction "S_29") (pintype "passive"))
    )
    (net (code "62") (name "A11") (class "Default")
      (node (ref "IC3") (pin "86") (pinfunction "PK3(ADC11/PCINT19)_86") (pintype "bidirectional"))
    )
    (net (code "63") (name "A12") (class "Default")
      (node (ref "IC3") (pin "85") (pinfunction "PK4(ADC12/PCINT20)_85") (pintype "bidirectional"))
    )
    (net (code "64") (name "A13") (class "Default")
      (node (ref "IC3") (pin "84") (pinfunction "PK5(ADC13/PCINT21)_84") (pintype "bidirectional"))
    )
    (net (code "65") (name "A14") (class "Default")
      (node (ref "IC3") (pin "83") (pinfunction "PK6(ADC14/PCINT22)_83") (pintype "bidirectional"))
    )
    (net (code "66") (name "A15") (class "Default")
      (node (ref "IC3") (pin "82") (pinfunction "PK7(ADC15/PCINT23)_82") (pintype "bidirectional"))
    )
    (net (code "67") (name "AREF") (class "Default")
      (node (ref "C3") (pin "1") (pinfunction "1_1") (pintype "passive"))
      (node (ref "IC3") (pin "98") (pinfunction "AREF_98") (pintype "bidirectional"))
    )
    (net (code "68") (name "CMP") (class "Default")
      (node (ref "C12") (pin "2") (pinfunction "2_2") (pintype "passive"))
      (node (ref "IC5") (pin "5") (pinfunction "+IN_5") (pintype "input"))
      (node (ref "RN5") (pin "3") (pinfunction "1_3") (pintype "passive"))
      (node (ref "RN5") (pin "7") (pinfunction "2_7") (pintype "passive"))
    )
    (net (code "69") (name "D+") (class "Default")
      (node (ref "J1") (pin "A6") (pinfunction "D+_A6") (pintype "bidirectional"))
      (node (ref "J1") (pin "B6") (pinfunction "D+_B6") (pintype "bidirectional"))
      (node (ref "RN2") (pin "5") (pinfunction "2_5") (pintype "passive"))
      (node (ref "Z2") (pin "2") (pinfunction "2_2") (pintype "passive"))
    )
    (net (code "70") (name "D-") (class "Default")
      (node (ref "J1") (pin "A7") (pinfunction "D-_A7") (pintype "bidirectional"))
      (node (ref "J1") (pin "B7") (pinfunction "D-_B7") (pintype "bidirectional"))
      (node (ref "RN2") (pin "8") (pinfunction "2_8") (pintype "passive"))
      (node (ref "Z1") (pin "2") (pinfunction "2_2") (pintype "passive"))
    )
    (net (code "71") (name "DTR") (class "Default")
      (node (ref "C7") (pin "1") (pinfunction "1_1") (pintype "passive"))
      (node (ref "IC4") (pin "13") (pinfunction "(CTS/HWB/AIN6/TO/INT7)PD7_13") (pintype "bidirectional"))
      (node (ref "UBOOT") (pin "1") (pinfunction "1_1") (pintype "passive"))
    )
    (net (code "72") (name "GATE_CMD") (class "Default")
      (node (ref "IC5") (pin "7") (pinfunction "OUT_7") (pintype "output"))
      (node (ref "T2") (pin "3") (pinfunction "G_3") (pintype "passive"))
    )
    (net (code "73") (name "GND") (class "Default")
      (node (ref "C1") (pin "2") (pinfunction "2_2") (pintype "passive"))
      (node (ref "C11") (pin "1") (pinfunction "1_1") (pintype "passive"))
      (node (ref "C12") (pin "1") (pinfunction "1_1") (pintype "passive"))
      (node (ref "C13") (pin "1") (pinfunction "1_1") (pintype "passive"))
      (node (ref "C14") (pin "1") (pinfunction "1_1") (pintype "passive"))
      (node (ref "C15") (pin "1") (pinfunction "1_1") (pintype "passive"))
      (node (ref "C2") (pin "2") (pinfunction "2_2") (pintype "passive"))
      (node (ref "C3") (pin "2") (pinfunction "2_2") (pintype "passive"))
      (node (ref "C4") (pin "2") (pinfunction "2_2") (pintype "passive"))
      (node (ref "C5") (pin "2") (pinfunction "2_2") (pintype "passive"))
      (node (ref "C6") (pin "2") (pinfunction "2_2") (pintype "passive"))
      (node (ref "C8") (pin "2") (pinfunction "2_2") (pintype "passive"))
      (node (ref "C9") (pin "2") (pinfunction "2_2") (pintype "passive"))
      (node (ref "CN1") (pin "GND") (pinfunction "GND_GND") (pintype "power_in"))
      (node (ref "CN1") (pin "GNDBREAK") (pinfunction "GNDBREAK_GNDBREAK") (pintype "power_in"))
      (node (ref "ENDSTOP") (pin "5") (pinfunction "KL_5") (pintype "passive"))
      (node (ref "ESTOP") (pin "3") (pinfunction "KL_3") (pintype "passive"))
      (node (ref "GROUND") (pin "2") (pinfunction "2_2") (pintype "passive"))
      (node (ref "IC1") (pin "1") (pinfunction "GND/ADJ_1") (pintype "input"))
      (node (ref "IC2") (pin "1") (pinfunction "ADJ_1") (pintype "input"))
      (node (ref "IC3") (pin "11") (pinfunction "GND_11") (pintype "power_in"))
      (node (ref "IC3") (pin "32") (pinfunction "GND1_32") (pintype "power_in"))
      (node (ref "IC3") (pin "62") (pinfunction "GND2_62") (pintype "power_in"))
      (node (ref "IC3") (pin "81") (pinfunction "GND3_81") (pintype "power_in"))
      (node (ref "IC3") (pin "99") (pinfunction "AGND_99") (pintype "power_in"))
      (node (ref "IC4") (pin "3") (pinfunction "GND_3") (pintype "power_in"))
      (node (ref "IC4") (pin "EXP") (pinfunction "PAD_EXP") (pintype "power_in"))
      (node (ref "IC5") (pin "2") (pinfunction "-IN_2") (pintype "input"))
      (node (ref "IC5") (pin "3") (pinfunction "+IN_3") (pintype "input"))
      (node (ref "IC5") (pin "4") (pinfunction "V-_4") (pintype "power_in"))
      (node (ref "IC6") (pin "2") (pinfunction "GND_2") (pintype "power_in"))
      (node (ref "L") (pin "C") (pinfunction "C_C") (pintype "passive"))
      (node (ref "MAGNET") (pin "2") (pinfunction "KL_2") (pintype "passive"))
      (node (ref "ON") (pin "C") (pinfunction "C_C") (pintype "passive"))
      (node (ref "PC1") (pin "-") (pinfunction "-_-") (pintype "passive"))
      (node (ref "PC2") (pin "-") (pinfunction "-_-") (pintype "passive"))
      (node (ref "RESET") (pin "1") (pinfunction "1_1") (pintype "passive"))
      (node (ref "RESET") (pin "2") (pinfunction "2_2") (pintype "passive"))
      (node (ref "RN5") (pin "2") (pinfunction "1_2") (pintype "passive"))
      (node (ref "SDCARD") (pin "GND") (pinfunction "GND_GND") (pintype "bidirectional"))
      (node (ref "SG1") (pin "-") (pinfunction "1_-") (pintype "passive"))
      (node (ref "STATUS_LED") (pin "2") (pinfunction "C_2") (pintype "bidirectional"))
      (node (ref "STEPPER-1-CON") (pin "GND") (pinfunction "GND_GND") (pintype "bidirectional"))
      (node (ref "STEPPER-2-CON") (pin "GND") (pinfunction "GND_GND") (pintype "bidirectional"))
      (node (ref "STEPPER-3-CON") (pin "GND") (pinfunction "GND_GND") (pintype "bidirectional"))
      (node (ref "U$1") (pin "GND") (pinfunction "GND_GND") (pintype "bidirectional"))
      (node (ref "UBOOT") (pin "2") (pinfunction "2_2") (pintype "passive"))
      (node (ref "X1") (pin "7") (pinfunction "S_7") (pintype "passive"))
      (node (ref "Y1") (pin "2") (pinfunction "2_2") (pintype "passive"))
      (node (ref "Y2") (pin "2") (pinfunction "2_2") (pintype "passive"))
    )
    (net (code "74") (name "HIGH_AMP_5V") (class "Default")
      (node (ref "C2") (pin "1") (pinfunction "1_1") (pintype "passive"))
      (node (ref "D1") (pin "C") (pinfunction "C_C") (pintype "passive"))
      (node (ref "IC1") (pin "3") (pinfunction "IN_3") (pintype "input"))
      (node (ref "IC2") (pin "3") (pinfunction "VI_3") (pintype "input"))
      (node (ref "PC1") (pin "+") (pinfunction "+_+") (pintype "passive"))
      (node (ref "RN5") (pin "6") (pinfunction "2_6") (pintype "passive"))
      (node (ref "STEPPER-1-CON") (pin "VM") (pinfunction "VM_VM") (pintype "bidirectional"))
      (node (ref "STEPPER-2-CON") (pin "VM") (pinfunction "VM_VM") (pintype "bidirectional"))
      (node (ref "STEPPER-3-CON") (pin "VM") (pinfunction "VM_VM") (pintype "bidirectional"))
      (node (ref "T1") (pin "C") (pinfunction "C_C") (pintype "passive"))
      (node (ref "X1") (pin "3") (pinfunction "S_3") (pintype "passive"))
    )
    (net (code "75") (name "M8RXD") (class "Default")
      (node (ref "IC4") (pin "9") (pinfunction "(TXD1/INT3)PD3_9") (pintype "bidirectional"))
      (node (ref "RN4") (pin "7") (pinfunction "2_7") (pintype "passive"))
    )
    (net (code "76") (name "M8TXD") (class "Default")
      (node (ref "IC4") (pin "8") (pinfunction "(RXD1/AIN1/INT2)PD2_8") (pintype "bidirectional"))
      (node (ref "RN4") (pin "8") (pinfunction "2_8") (pintype "passive"))
    )
    (net (code "77") (name "MISO2") (class "Default")
      (node (ref "IC4") (pin "17") (pinfunction "(PD0/MISO/PCINT3)PB3_17") (pintype "bidirectional"))
    )
    (net (code "78") (name "MOSI2") (class "Default")
      (node (ref "IC4") (pin "16") (pinfunction "(PDI/MOSI/PCINT2)PB2_16") (pintype "bidirectional"))
    )
    (net (code "79") (name "Net-(MAGNETA-KL)") (class "Default")
      (node (ref "MAGNET") (pin "1") (pinfunction "KL_1") (pintype "passive"))
      (node (ref "T1") (pin "E") (pinfunction "E_E") (pintype "passive"))
    )
    (net (code "80") (name "Net-(POWERB-KL)") (class "Default")
      (node (ref "CN1") (pin "PWR") (pinfunction "PWR_PWR") (pintype "power_in"))
      (node (ref "POWER") (pin "2") (pinfunction "KL_2") (pintype "passive"))
    )
    (net (code "81") (name "Net-(RN3C-2)") (class "Default")
      (node (ref "ON") (pin "A") (pinfunction "A_A") (pintype "passive"))
      (node (ref "RN3") (pin "6") (pinfunction "2_6") (pintype "passive"))
    )
    (net (code "82") (name "Net-(RN3D-1)") (class "Default")
      (node (ref "L") (pin "A") (pinfunction "A_A") (pintype "passive"))
      (node (ref "RN3") (pin "4") (pinfunction "1_4") (pintype "passive"))
    )
    (net (code "83") (name "Net-(RN4C-1)") (class "Default")
      (node (ref "RN4") (pin "3") (pinfunction "1_3") (pintype "passive"))
      (node (ref "TX") (pin "A") (pinfunction "A_A") (pintype "passive"))
    )
    (net (code "84") (name "Net-(RN4D-1)") (class "Default")
      (node (ref "RN4") (pin "4") (pinfunction "1_4") (pintype "passive"))
      (node (ref "RX") (pin "A") (pinfunction "A_A") (pintype "passive"))
    )
    (net (code "85") (name "Net-(STATUS_LED-BLU)") (class "Default")
      (node (ref "R2") (pin "2") (pinfunction "2_2") (pintype "passive"))
      (node (ref "STATUS_LED") (pin "4") (pinfunction "BLU_4") (pintype "bidirectional"))
    )
    (net (code "86") (name "Net-(STATUS_LED-GRN)") (class "Default")
      (node (ref "R3") (pin "2") (pinfunction "2_2") (pintype "passive"))
      (node (ref "STATUS_LED") (pin "3") (pinfunction "GRN_3") (pintype "bidirectional"))
    )
    (net (code "87") (name "Net-(STATUS_LED-RED)") (class "Default")
      (node (ref "R1") (pin "2") (pinfunction "2_2") (pintype "passive"))
      (node (ref "STATUS_LED") (pin "1") (pinfunction "RED_1") (pintype "bidirectional"))
    )
    (net (code "88") (name "Net-(STEPPER-1-CON-PadMOTORA-1)") (class "Default")
      (node (ref "STEPPER-1") (pin "3") (pinfunction "3_3") (pintype "passive"))
      (node (ref "STEPPER-1-CON") (pin "MOTORA-1") (pinfunction "MOTORA-1_MOTORA-1") (pintype "bidirectional"))
    )
    (net (code "89") (name "Net-(STEPPER-1-CON-PadMOTORA-2)") (class "Default")
      (node (ref "STEPPER-1") (pin "4") (pinfunction "4_4") (pintype "passive"))
      (node (ref "STEPPER-1-CON") (pin "MOTORA-2") (pinfunction "MOTORA-2_MOTORA-2") (pintype "bidirectional"))
    )
    (net (code "90") (name "Net-(STEPPER-1-CON-PadMOTORB-1)") (class "Default")
      (node (ref "STEPPER-1") (pin "2") (pinfunction "2_2") (pintype "passive"))
      (node (ref "STEPPER-1-CON") (pin "MOTORB-1") (pinfunction "MOTORB-1_MOTORB-1") (pintype "bidirectional"))
    )
    (net (code "91") (name "Net-(STEPPER-1-CON-PadMOTORB-2)") (class "Default")
      (node (ref "STEPPER-1") (pin "1") (pinfunction "1_1") (pintype "passive"))
      (node (ref "STEPPER-1-CON") (pin "MOTORB-2") (pinfunction "MOTORB-2_MOTORB-2") (pintype "bidirectional"))
    )
    (net (code "92") (name "Net-(STEPPER-2-CON-PadMOTORA-1)") (class "Default")
      (node (ref "STEPPER-2") (pin "3") (pinfunction "3_3") (pintype "passive"))
      (node (ref "STEPPER-2-CON") (pin "MOTORA-1") (pinfunction "MOTORA-1_MOTORA-1") (pintype "bidirectional"))
    )
    (net (code "93") (name "Net-(STEPPER-2-CON-PadMOTORA-2)") (class "Default")
      (node (ref "STEPPER-2") (pin "4") (pinfunction "4_4") (pintype "passive"))
      (node (ref "STEPPER-2-CON") (pin "MOTORA-2") (pinfunction "MOTORA-2_MOTORA-2") (pintype "bidirectional"))
    )
    (net (code "94") (name "Net-(STEPPER-2-CON-PadMOTORB-1)") (class "Default")
      (node (ref "STEPPER-2") (pin "2") (pinfunction "2_2") (pintype "passive"))
      (node (ref "STEPPER-2-CON") (pin "MOTORB-1") (pinfunction "MOTORB-1_MOTORB-1") (pintype "bidirectional"))
    )
    (net (code "95") (name "Net-(STEPPER-2-CON-PadMOTORB-2)") (class "Default")
      (node (ref "STEPPER-2") (pin "1") (pinfunction "1_1") (pintype "passive"))
      (node (ref "STEPPER-2-CON") (pin "MOTORB-2") (pinfunction "MOTORB-2_MOTORB-2") (pintype "bidirectional"))
    )
    (net (code "96") (name "Net-(STEPPER-3-CON-PadMOTORA-1)") (class "Default")
      (node (ref "STEPPER-3") (pin "3") (pinfunction "3_3") (pintype "passive"))
      (node (ref "STEPPER-3-CON") (pin "MOTORA-1") (pinfunction "MOTORA-1_MOTORA-1") (pintype "bidirectional"))
    )
    (net (code "97") (name "Net-(STEPPER-3-CON-PadMOTORA-2)") (class "Default")
      (node (ref "STEPPER-3") (pin "4") (pinfunction "4_4") (pintype "passive"))
      (node (ref "STEPPER-3-CON") (pin "MOTORA-2") (pinfunction "MOTORA-2_MOTORA-2") (pintype "bidirectional"))
    )
    (net (code "98") (name "Net-(STEPPER-3-CON-PadMOTORB-1)") (class "Default")
      (node (ref "STEPPER-3") (pin "2") (pinfunction "2_2") (pintype "passive"))
      (node (ref "STEPPER-3-CON") (pin "MOTORB-1") (pinfunction "MOTORB-1_MOTORB-1") (pintype "bidirectional"))
    )
    (net (code "99") (name "Net-(STEPPER-3-CON-PadMOTORB-2)") (class "Default")
      (node (ref "STEPPER-3") (pin "1") (pinfunction "1_1") (pintype "passive"))
      (node (ref "STEPPER-3-CON") (pin "MOTORB-2") (pinfunction "MOTORB-2_MOTORB-2") (pintype "bidirectional"))
    )
    (net (code "100") (name "PWRIN") (class "Default")
      (node (ref "D1") (pin "A") (pinfunction "A_A") (pintype "passive"))
      (node (ref "POWER") (pin "1") (pinfunction "KL_1") (pintype "passive"))
    )
    (net (code "101") (name "RD+") (class "Default")
      (node (ref "IC4") (pin "29") (pinfunction "D+_29") (pintype "bidirectional"))
      (node (ref "RN2") (pin "4") (pinfunction "1_4") (pintype "passive"))
    )
    (net (code "102") (name "RD-") (class "Default")
      (node (ref "IC4") (pin "30") (pinfunction "D-_30") (pintype "bidirectional"))
      (node (ref "RN2") (pin "1") (pinfunction "1_1") (pintype "passive"))
    )
    (net (code "103") (name "RESET") (class "Default")
      (node (ref "C1") (pin "1") (pinfunction "1_1") (pintype "passive"))
      (node (ref "C7") (pin "2") (pinfunction "2_2") (pintype "passive"))
      (node (ref "IC3") (pin "30") (pinfunction "RESET_30") (pintype "input"))
      (node (ref "RESET") (pin "3") (pinfunction "3_3") (pintype "passive"))
      (node (ref "RESET") (pin "4") (pinfunction "4_4") (pintype "passive"))
      (node (ref "RESET-EN") (pin "1") (pinfunction "1_1") (pintype "passive"))
      (node (ref "RESET-EN") (pin "2") (pinfunction "2_2") (pintype "passive"))
      (node (ref "RN1") (pin "1") (pinfunction "1_1") (pintype "passive"))
    )
    (net (code "104") (name "RESET2") (class "Default")
      (node (ref "IC4") (pin "24") (pinfunction "RESET(PC1/DW)_24") (pintype "input"))
      (node (ref "RN5") (pin "8") (pinfunction "2_8") (pintype "passive"))
    )
    (net (code "105") (name "RX0") (class "Default")
      (node (ref "IC3") (pin "2") (pinfunction "(RXD0/PCIN8)PE0_2") (pintype "bidirectional"))
      (node (ref "RN4") (pin "2") (pinfunction "1_2") (pintype "passive"))
    )
    (net (code "106") (name "RX1") (class "Default")
      (node (ref "IC3") (pin "45") (pinfunction "(RXD1/INT2)PD2_45") (pintype "bidirectional"))
    )
    (net (code "107") (name "RX2") (class "Default")
      (node (ref "IC3") (pin "12") (pinfunction "PH0(RXD2)_12") (pintype "bidirectional"))
    )
    (net (code "108") (name "RX3") (class "Default")
      (node (ref "IC3") (pin "63") (pinfunction "PJ0(RXD3/PCINT9)_63") (pintype "bidirectional"))
    )
    (net (code "109") (name "RXL") (class "Default")
      (node (ref "IC4") (pin "10") (pinfunction "(INT5/AIN3)PD4_10") (pintype "bidirectional"))
      (node (ref "RX") (pin "C") (pinfunction "C_C") (pintype "passive"))
    )
    (net (code "110") (name "SCK2") (class "Default")
      (node (ref "IC4") (pin "15") (pinfunction "(SCLK/PCINT1)PB1_15") (pintype "bidirectional"))
    )
    (net (code "111") (name "SCL") (class "Default")
      (node (ref "RN1") (pin "2") (pinfunction "1_2") (pintype "passive"))
    )
    (net (code "112") (name "SDA") (class "Default")
      (node (ref "RN1") (pin "3") (pinfunction "1_3") (pintype "passive"))
    )
    (net (code "113") (name "TX0") (class "Default")
      (node (ref "IC3") (pin "3") (pinfunction "(TXD0)PE1_3") (pintype "bidirectional"))
      (node (ref "RN4") (pin "1") (pinfunction "1_1") (pintype "passive"))
    )
    (net (code "114") (name "TX1") (class "Default")
      (node (ref "IC3") (pin "46") (pinfunction "(TXD1/INT3)PD3_46") (pintype "bidirectional"))
    )
    (net (code "115") (name "TX2") (class "Default")
      (node (ref "IC3") (pin "13") (pinfunction "PH1(TXD2)_13") (pintype "bidirectional"))
    )
    (net (code "116") (name "TX3") (class "Default")
      (node (ref "IC3") (pin "64") (pinfunction "PJ1(TXD3/PCINT10)_64") (pintype "bidirectional"))
    )
    (net (code "117") (name "TXL") (class "Default")
      (node (ref "IC4") (pin "11") (pinfunction "(XCK/AIN4/PCINT12)PD5_11") (pintype "bidirectional"))
      (node (ref "TX") (pin "C") (pinfunction "C_C") (pintype "passive"))
    )
    (net (code "118") (name "UGND") (class "Default")
      (node (ref "C10") (pin "2") (pinfunction "2_2") (pintype "passive"))
      (node (ref "GROUND") (pin "1") (pinfunction "1_1") (pintype "passive"))
      (node (ref "IC4") (pin "28") (pinfunction "UGND_28") (pintype "power_in"))
      (node (ref "J1") (pin "GND") (pinfunction "GND_GND") (pintype "bidirectional"))
      (node (ref "J1") (pin "GND2") (pinfunction "GND_GND2") (pintype "bidirectional"))
      (node (ref "L1") (pin "1") (pinfunction "1_1") (pintype "passive"))
    )
    (net (code "119") (name "USBVCC") (class "Default")
      (node (ref "C8") (pin "1") (pinfunction "1_1") (pintype "passive"))
      (node (ref "F1") (pin "1") (pinfunction "1_1") (pintype "passive"))
      (node (ref "IC4") (pin "31") (pinfunction "UVCC_31") (pintype "power_in"))
      (node (ref "T2") (pin "1") (pinfunction "D_1") (pintype "passive"))
    )
    (net (code "120") (name "USHIELD") (class "Default")
      (node (ref "J1") (pin "SHLD1") (pinfunction "SHLD_SHLD1") (pintype "bidirectional"))
      (node (ref "J1") (pin "SHLD2") (pinfunction "SHLD_SHLD2") (pintype "bidirectional"))
      (node (ref "J1") (pin "SHLD3") (pinfunction "SHLD_SHLD3") (pintype "bidirectional"))
      (node (ref "J1") (pin "SHLD4") (pinfunction "SHLD_SHLD4") (pintype "bidirectional"))
      (node (ref "L1") (pin "2") (pinfunction "2_2") (pintype "passive"))
      (node (ref "Z1") (pin "1") (pinfunction "1_1") (pintype "passive"))
      (node (ref "Z2") (pin "1") (pinfunction "1_1") (pintype "passive"))
    )
    (net (code "121") (name "VUCAP") (class "Default")
      (node (ref "C10") (pin "1") (pinfunction "1_1") (pintype "passive"))
      (node (ref "IC4") (pin "27") (pinfunction "UCAP_27") (pintype "passive"))
    )
    (net (code "122") (name "XT1R") (class "Default")
      (node (ref "IC4") (pin "1") (pinfunction "XTAL1_1") (pintype "bidirectional"))
      (node (ref "R7") (pin "1") (pinfunction "1_1") (pintype "passive"))
    )
    (net (code "123") (name "XTAL1") (class "Default")
      (node (ref "C14") (pin "2") (pinfunction "2_2") (pintype "passive"))
      (node (ref "Q2") (pin "2") (pinfunction "2_2") (pintype "passive"))
      (node (ref "R4") (pin "1") (pinfunction "1_1") (pintype "passive"))
      (node (ref "R5") (pin "1") (pinfunction "1_1") (pintype "passive"))
      (node (ref "R6") (pin "2") (pinfunction "2_2") (pintype "passive"))
      (node (ref "R7") (pin "2") (pinfunction "2_2") (pintype "passive"))
      (node (ref "Y1") (pin "3") (pinfunction "3_3") (pintype "passive"))
      (node (ref "Y2") (pin "3") (pinfunction "3_3") (pintype "passive"))
    )
    (net (code "124") (name "XTAL1R") (class "Default")
      (node (ref "IC3") (pin "34") (pinfunction "XTAL1_34") (pintype "input"))
      (node (ref "R6") (pin "1") (pinfunction "1_1") (pintype "passive"))
    )
    (net (code "125") (name "XTAL2") (class "Default")
      (node (ref "C15") (pin "2") (pinfunction "2_2") (pintype "passive"))
      (node (ref "IC3") (pin "33") (pinfunction "XTAL2_33") (pintype "output"))
      (node (ref "IC4") (pin "2") (pinfunction "XTAL2(PC0)_2") (pintype "bidirectional"))
      (node (ref "Q2") (pin "1") (pinfunction "1_1") (pintype "passive"))
      (node (ref "R4") (pin "2") (pinfunction "2_2") (pintype "passive"))
      (node (ref "R5") (pin "2") (pinfunction "2_2") (pintype "passive"))
      (node (ref "Y1") (pin "1") (pinfunction "1_1") (pintype "passive"))
      (node (ref "Y2") (pin "1") (pinfunction "1_1") (pintype "passive"))
    )
    (net (code "126") (name "XVCC") (class "Default")
      (node (ref "F1") (pin "2") (pinfunction "2_2") (pintype "passive"))
      (node (ref "J1") (pin "VBUS1") (pinfunction "VBUS_VBUS1") (pintype "bidirectional"))
      (node (ref "J1") (pin "VBUS2") (pinfunction "VBUS_VBUS2") (pintype "bidirectional"))
    )
    (net (code "127") (name "unconnected-(IC3-(CLKO{slash}ICP3{slash}INT7)PE7-Pad9)") (class "Default")
      (node (ref "IC3") (pin "9") (pinfunction "(CLKO/ICP3/INT7)PE7_9") (pintype "bidirectional"))
    )
    (net (code "128") (name "unconnected-(IC3-(ICP1)PD4-Pad47)") (class "Default")
      (node (ref "IC3") (pin "47") (pinfunction "(ICP1)PD4_47") (pintype "bidirectional"))
    )
    (net (code "129") (name "unconnected-(IC3-(T1)PD6-Pad49)") (class "Default")
      (node (ref "IC3") (pin "49") (pinfunction "(T1)PD6_49") (pintype "bidirectional"))
    )
    (net (code "130") (name "unconnected-(IC3-(T3{slash}INT6)PE6-Pad8)") (class "Default")
      (node (ref "IC3") (pin "8") (pinfunction "(T3/INT6)PE6_8") (pintype "bidirectional"))
    )
    (net (code "131") (name "unconnected-(IC3-(TOSC1)PG4-Pad29)") (class "Default")
      (node (ref "IC3") (pin "29") (pinfunction "(TOSC1)PG4_29") (pintype "bidirectional"))
    )
    (net (code "132") (name "unconnected-(IC3-(TOSC2)PG3-Pad28)") (class "Default")
      (node (ref "IC3") (pin "28") (pinfunction "(TOSC2)PG3_28") (pintype "bidirectional"))
    )
    (net (code "133") (name "unconnected-(IC3-(XCK0{slash}AIN0)PE2-Pad4)") (class "Default")
      (node (ref "IC3") (pin "4") (pinfunction "(XCK0/AIN0)PE2_4") (pintype "bidirectional"))
    )
    (net (code "134") (name "unconnected-(IC3-(XCK1)PD5-Pad48)") (class "Default")
      (node (ref "IC3") (pin "48") (pinfunction "(XCK1)PD5_48") (pintype "bidirectional"))
    )
    (net (code "135") (name "unconnected-(IC3-PH2(XCK2)-Pad14)") (class "Default")
      (node (ref "IC3") (pin "14") (pinfunction "PH2(XCK2)_14") (pintype "bidirectional"))
    )
    (net (code "136") (name "unconnected-(IC3-PH7(T4)-Pad27)") (class "Default")
      (node (ref "IC3") (pin "27") (pinfunction "PH7(T4)_27") (pintype "bidirectional"))
    )
    (net (code "137") (name "unconnected-(IC3-PJ2(XCK3{slash}PCINT11)-Pad65)") (class "Default")
      (node (ref "IC3") (pin "65") (pinfunction "PJ2(XCK3/PCINT11)_65") (pintype "bidirectional"))
    )
    (net (code "138") (name "unconnected-(IC3-PJ3(PCINT12)-Pad66)") (class "Default")
      (node (ref "IC3") (pin "66") (pinfunction "PJ3(PCINT12)_66") (pintype "bidirectional"))
    )
    (net (code "139") (name "unconnected-(IC3-PJ4(PCINT13)-Pad67)") (class "Default")
      (node (ref "IC3") (pin "67") (pinfunction "PJ4(PCINT13)_67") (pintype "bidirectional"))
    )
    (net (code "140") (name "unconnected-(IC3-PJ5(PCINT14)-Pad68)") (class "Default")
      (node (ref "IC3") (pin "68") (pinfunction "PJ5(PCINT14)_68") (pintype "bidirectional"))
    )
    (net (code "141") (name "unconnected-(IC3-PJ6(PCINT15)-Pad69)") (class "Default")
      (node (ref "IC3") (pin "69") (pinfunction "PJ6(PCINT15)_69") (pintype "bidirectional"))
    )
    (net (code "142") (name "unconnected-(IC3-PJ7-Pad79)") (class "Default")
      (node (ref "IC3") (pin "79") (pinfunction "PJ7_79") (pintype "bidirectional"))
    )
    (net (code "143") (name "unconnected-(IC4-(AIN0{slash}INT1)PD1-Pad7)") (class "Default")
      (node (ref "IC4") (pin "7") (pinfunction "(AIN0/INT1)PD1_7") (pintype "bidirectional"))
    )
    (net (code "144") (name "unconnected-(IC4-(AIN2{slash}PCINT11)PC2-Pad5)") (class "Default")
      (node (ref "IC4") (pin "5") (pinfunction "(AIN2/PCINT11)PC2_5") (pintype "bidirectional"))
    )
    (net (code "145") (name "unconnected-(IC4-(INT4{slash}ICP1{slash}CLK0)PC7-Pad22)") (class "Default")
      (node (ref "IC4") (pin "22") (pinfunction "(INT4/ICP1/CLK0)PC7_22") (pintype "bidirectional"))
    )
    (net (code "146") (name "unconnected-(IC4-(OC0B{slash}INT0)PD0-Pad6)") (class "Default")
      (node (ref "IC4") (pin "6") (pinfunction "(OC0B/INT0)PD0_6") (pintype "bidirectional"))
    )
    (net (code "147") (name "unconnected-(IC4-(OC1A{slash}PCINT8)PC6-Pad23)") (class "Default")
      (node (ref "IC4") (pin "23") (pinfunction "(OC1A/PCINT8)PC6_23") (pintype "bidirectional"))
    )
    (net (code "148") (name "unconnected-(IC4-(PCINT5)PB5-Pad19)") (class "Default")
      (node (ref "IC4") (pin "19") (pinfunction "(PCINT5)PB5_19") (pintype "bidirectional"))
    )
    (net (code "149") (name "unconnected-(IC4-(PCINT6)PB6-Pad20)") (class "Default")
      (node (ref "IC4") (pin "20") (pinfunction "(PCINT6)PB6_20") (pintype "bidirectional"))
    )
    (net (code "150") (name "unconnected-(IC4-(PCINT7{slash}OC0A{slash}OC1C)PB7-Pad21)") (class "Default")
      (node (ref "IC4") (pin "21") (pinfunction "(PCINT7/OC0A/OC1C)PB7_21") (pintype "bidirectional"))
    )
    (net (code "151") (name "unconnected-(IC4-(PCINT9{slash}OC1B)PC5-Pad25)") (class "Default")
      (node (ref "IC4") (pin "25") (pinfunction "(PCINT9/OC1B)PC5_25") (pintype "bidirectional"))
    )
    (net (code "152") (name "unconnected-(IC4-(PCINT10)PC4-Pad26)") (class "Default")
      (node (ref "IC4") (pin "26") (pinfunction "(PCINT10)PC4_26") (pintype "bidirectional"))
    )
    (net (code "153") (name "unconnected-(IC4-(RTS{slash}AIN5{slash}INT6)PD6-Pad12)") (class "Default")
      (node (ref "IC4") (pin "12") (pinfunction "(RTS/AIN5/INT6)PD6_12") (pintype "bidirectional"))
    )
    (net (code "154") (name "unconnected-(IC4-(SS{slash}PCINT0)PB0-Pad14)") (class "Default")
      (node (ref "IC4") (pin "14") (pinfunction "(SS/PCINT0)PB0_14") (pintype "bidirectional"))
    )
    (net (code "155") (name "unconnected-(IC4-(T1{slash}PCINT4)PB4-Pad18)") (class "Default")
      (node (ref "IC4") (pin "18") (pinfunction "(T1/PCINT4)PB4_18") (pintype "bidirectional"))
    )
    (net (code "156") (name "unconnected-(IC5A-OUT-Pad1)") (class "Default")
      (node (ref "IC5") (pin "1") (pinfunction "OUT_1") (pintype "output"))
    )
    (net (code "157") (name "unconnected-(IC6-NC{slash}FB-Pad4)") (class "Default")
      (node (ref "IC6") (pin "4") (pinfunction "NC/FB_4") (pintype "passive"))
    )
    (net (code "158") (name "unconnected-(J1-CC1-PadA5)") (class "Default")
      (node (ref "J1") (pin "A5") (pinfunction "CC1_A5") (pintype "bidirectional"))
    )
    (net (code "159") (name "unconnected-(J1-CC2-PadB5)") (class "Default")
      (node (ref "J1") (pin "B5") (pinfunction "CC2_B5") (pintype "bidirectional"))
    )
    (net (code "160") (name "unconnected-(RN1D-1-Pad4)") (class "Default")
      (node (ref "RN1") (pin "4") (pinfunction "1_4") (pintype "passive"))
    )
    (net (code "161") (name "unconnected-(RN1D-2-Pad5)") (class "Default")
      (node (ref "RN1") (pin "5") (pinfunction "2_5") (pintype "passive"))
    )
    (net (code "162") (name "unconnected-(RN2B-1-Pad2)") (class "Default")
      (node (ref "RN2") (pin "2") (pinfunction "1_2") (pintype "passive"))
    )
    (net (code "163") (name "unconnected-(RN2B-2-Pad7)") (class "Default")
      (node (ref "RN2") (pin "7") (pinfunction "2_7") (pintype "passive"))
    )
    (net (code "164") (name "unconnected-(RN2C-1-Pad3)") (class "Default")
      (node (ref "RN2") (pin "3") (pinfunction "1_3") (pintype "passive"))
    )
    (net (code "165") (name "unconnected-(RN2C-2-Pad6)") (class "Default")
      (node (ref "RN2") (pin "6") (pinfunction "2_6") (pintype "passive"))
    )
    (net (code "166") (name "unconnected-(RN3-Pad1)") (class "Default")
      (node (ref "RN3") (pin "1") (pinfunction "1_1") (pintype "passive"))
    )
    (net (code "167") (name "unconnected-(RN3A-2-Pad8)") (class "Default")
      (node (ref "RN3") (pin "8") (pinfunction "2_8") (pintype "passive"))
    )
    (net (code "168") (name "unconnected-(RN3B-1-Pad2)") (class "Default")
      (node (ref "RN3") (pin "2") (pinfunction "1_2") (pintype "passive"))
    )
    (net (code "169") (name "unconnected-(RN3B-2-Pad7)") (class "Default")
      (node (ref "RN3") (pin "7") (pinfunction "2_7") (pintype "passive"))
    )
    (net (code "170") (name "unconnected-(RN5D-1-Pad4)") (class "Default")
      (node (ref "RN5") (pin "4") (pinfunction "1_4") (pintype "passive"))
    )
    (net (code "171") (name "unconnected-(RN5D-2-Pad5)") (class "Default")
      (node (ref "RN5") (pin "5") (pinfunction "2_5") (pintype "passive"))
    )
    (net (code "172") (name "unconnected-(SDCARD-Pad3V)") (class "Default")
      (node (ref "SDCARD") (pin "3V") (pinfunction "3V_3V") (pintype "bidirectional"))
    )
    (net (code "173") (name "unconnected-(SDCARD-PadCD)") (class "Default")
      (node (ref "SDCARD") (pin "CD") (pinfunction "CD_CD") (pintype "bidirectional"))
    )
    (net (code "174") (name "unconnected-(STEPPER-1-CON-PadGND-1)") (class "Default")
      (node (ref "STEPPER-1-CON") (pin "GND-1") (pinfunction "GND-1_GND-1") (pintype "bidirectional"))
    )
    (net (code "175") (name "unconnected-(STEPPER-1-CON-PadGND-2)") (class "Default")
      (node (ref "STEPPER-1-CON") (pin "GND-2") (pinfunction "GND-2_GND-2") (pintype "bidirectional"))
    )
    (net (code "176") (name "unconnected-(STEPPER-2-CON-PadGND-1)") (class "Default")
      (node (ref "STEPPER-2-CON") (pin "GND-1") (pinfunction "GND-1_GND-1") (pintype "bidirectional"))
    )
    (net (code "177") (name "unconnected-(STEPPER-2-CON-PadGND-2)") (class "Default")
      (node (ref "STEPPER-2-CON") (pin "GND-2") (pinfunction "GND-2_GND-2") (pintype "bidirectional"))
    )
    (net (code "178") (name "unconnected-(STEPPER-3-CON-PadGND-1)") (class "Default")
      (node (ref "STEPPER-3-CON") (pin "GND-1") (pinfunction "GND-1_GND-1") (pintype "bidirectional"))
    )
    (net (code "179") (name "unconnected-(STEPPER-3-CON-PadGND-2)") (class "Default")
      (node (ref "STEPPER-3-CON") (pin "GND-2") (pinfunction "GND-2_GND-2") (pintype "bidirectional"))
    )
    (net (code "180") (name "unconnected-(U$1-PadIRQ)") (class "Default")
      (node (ref "U$1") (pin "IRQ") (pinfunction "IRQ_IRQ") (pintype "bidirectional"))
    )
    (net (code "181") (name "unconnected-(X1AM-S-Pad8)") (class "Default")
      (node (ref "X1") (pin "8") (pinfunction "S_8") (pintype "passive"))
    )
    (net (code "182") (name "unconnected-(X1B-S-Pad10)") (class "Default")
      (node (ref "X1") (pin "10") (pinfunction "S_10") (pintype "passive"))
    )
    (net (code "183") (name "unconnected-(X1D-S-Pad12)") (class "Default")
      (node (ref "X1") (pin "12") (pinfunction "S_12") (pintype "passive"))
    )
    (net (code "184") (name "unconnected-(X1F-S-Pad14)") (class "Default")
      (node (ref "X1") (pin "14") (pinfunction "S_14") (pintype "passive"))
    )
    (net (code "185") (name "unconnected-(X1H-S-Pad16)") (class "Default")
      (node (ref "X1") (pin "16") (pinfunction "S_16") (pintype "passive"))
    )
    (net (code "186") (name "unconnected-(X1J-S-Pad18)") (class "Default")
      (node (ref "X1") (pin "18") (pinfunction "S_18") (pintype "passive"))
    )
    (net (code "187") (name "unconnected-(X1M-S-Pad20)") (class "Default")
      (node (ref "X1") (pin "20") (pinfunction "S_20") (pintype "passive"))
    )
  )
)
